# Top_Level.net
KiCad netlist of a schematic drawn in Altium Designer
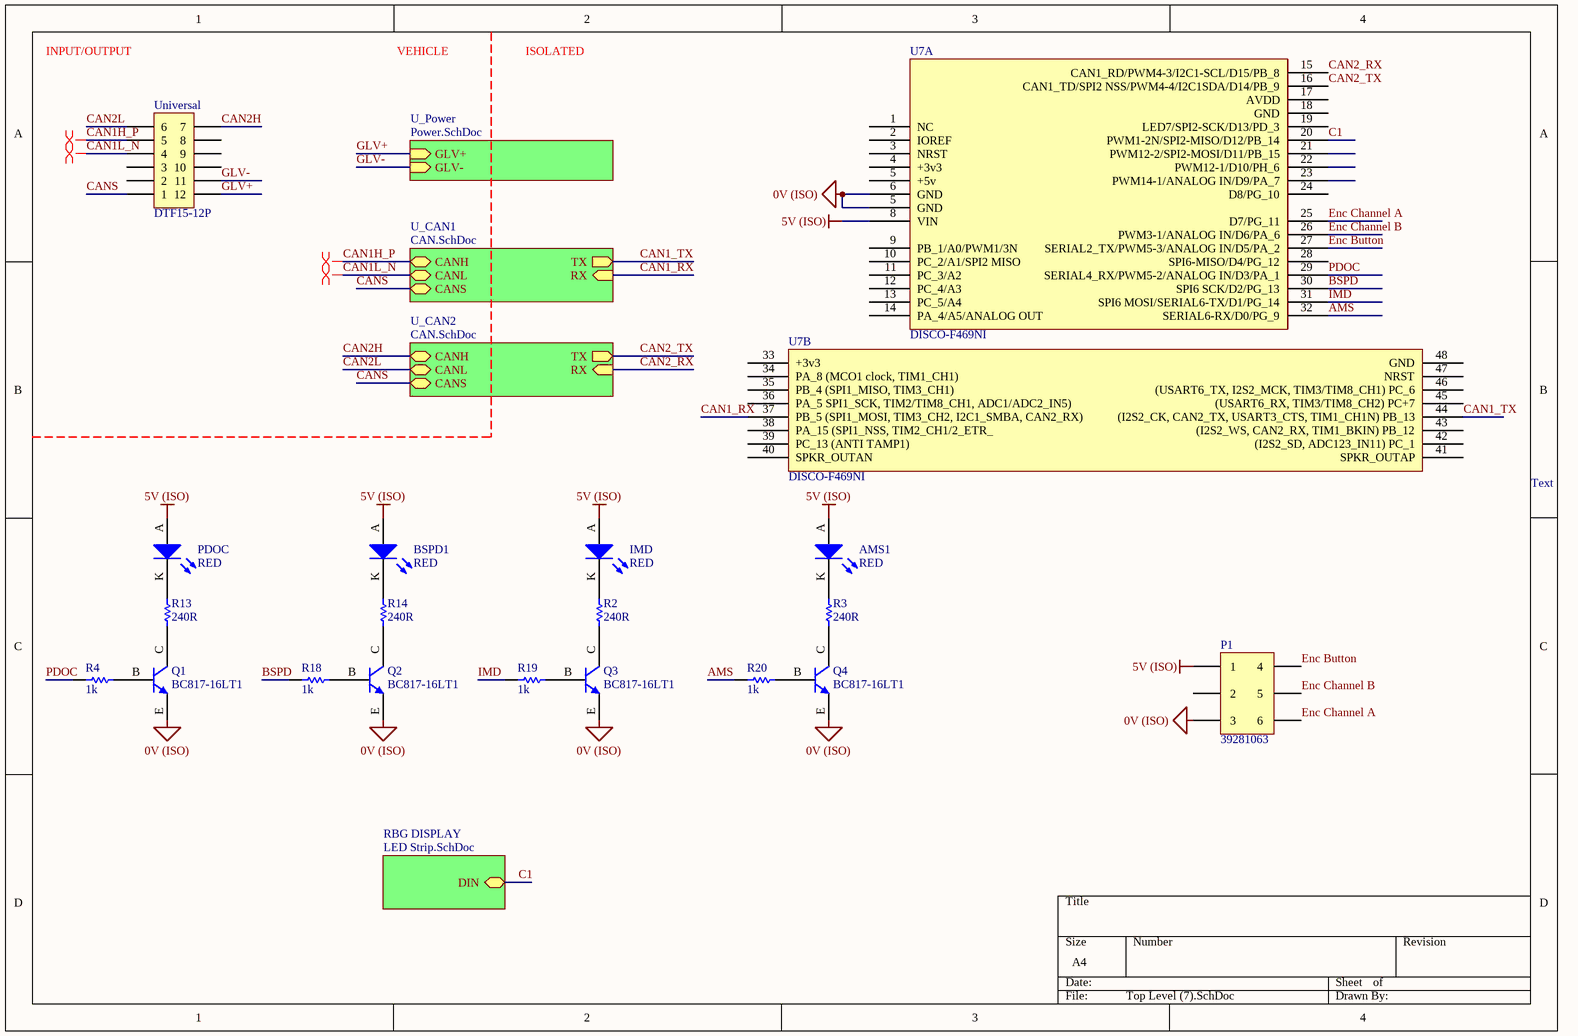
[diagram p0: Top Level (7).SchDoc]

(export (version "E")
  (design (tool "Eeschema 10.0.6"))
  (components
    (comp (ref "AMS1")
      (value "RED")
      (footprint "5MM LED")
      (description "LED RED CLEAR 5MM ROUND T/H")
      (fields (field (name "PART NUMBER") "C503B-GAN-CB0F0791") (field (name "MANUFACTURER") "Cree Inc."))
      (libsource (lib "ts_19-standard-library") (part "LED"))
    )
    (comp (ref "BSPD1")
      (value "RED")
      (footprint "5MM LED")
      (description "LED RED CLEAR 5MM ROUND T/H")
      (fields (field (name "PART NUMBER") "C503B-GAN-CB0F0791") (field (name "MANUFACTURER") "Cree Inc."))
      (libsource (lib "ts_19-standard-library") (part "LED"))
    )
    (comp (ref "IMD")
      (value "RED")
      (footprint "5MM LED")
      (description "LED RED CLEAR 5MM ROUND T/H")
      (fields (field (name "PART NUMBER") "C503B-GAN-CB0F0791") (field (name "MANUFACTURER") "Cree Inc."))
      (libsource (lib "ts_19-standard-library") (part "LED"))
    )
    (comp (ref "P1")
      (value "39281063")
      (footprint "39281063")
      (description "Mini-Fit VERT 3x2")
      (fields (field (name "DIGIKEY PART NUMBER") "WM3802-ND") (field (name "CONTACT") "Gold"))
      (libsource (lib "ts_19-standard-connectors") (part "39281063"))
    )
    (comp (ref "PDOC")
      (value "RED")
      (footprint "5MM LED")
      (description "LED RED CLEAR 5MM ROUND T/H")
      (fields (field (name "PART NUMBER") "C503B-GAN-CB0F0791") (field (name "MANUFACTURER") "Cree Inc."))
      (libsource (lib "ts_19-standard-library") (part "LED"))
    )
    (comp (ref "Q1")
      (value "BC817-16LT1")
      (footprint "ON SOT-23 BJT")
      (description "300mW  BJT NPN Transistor")
      (fields
        (field (name "MANUFACTURER") "ON Semiconductor")
        (field (name "DIGIKEY PART NUMBER") "BC817-16LT1OSTR-ND")
      )
      (libsource (lib "ts_19-standard-library") (part "NPN"))
    )
    (comp (ref "Q2")
      (value "BC817-16LT1")
      (footprint "ON SOT-23 BJT")
      (description "300mW  BJT NPN Transistor")
      (fields
        (field (name "MANUFACTURER") "ON Semiconductor")
        (field (name "DIGIKEY PART NUMBER") "BC817-16LT1OSTR-ND")
      )
      (libsource (lib "ts_19-standard-library") (part "NPN"))
    )
    (comp (ref "Q3")
      (value "BC817-16LT1")
      (footprint "ON SOT-23 BJT")
      (description "300mW  BJT NPN Transistor")
      (fields
        (field (name "MANUFACTURER") "ON Semiconductor")
        (field (name "DIGIKEY PART NUMBER") "BC817-16LT1OSTR-ND")
      )
      (libsource (lib "ts_19-standard-library") (part "NPN"))
    )
    (comp (ref "Q4")
      (value "BC817-16LT1")
      (footprint "ON SOT-23 BJT")
      (description "300mW  BJT NPN Transistor")
      (fields
        (field (name "MANUFACTURER") "ON Semiconductor")
        (field (name "DIGIKEY PART NUMBER") "BC817-16LT1OSTR-ND")
      )
      (libsource (lib "ts_19-standard-library") (part "NPN"))
    )
    (comp (ref "R2")
      (value "240R")
      (footprint "0805")
      (fields
        (field (name "PART NUMBER") "RC0805FR07240RL")
        (field (name "MANUFACTURER") "YAGEO")
        (field (name "TOLERANCE") "0.01")
      )
      (libsource (lib "ts_19-standard-library") (part "Resistor"))
    )
    (comp (ref "R3")
      (value "240R")
      (footprint "0805")
      (fields
        (field (name "PART NUMBER") "RC0805FR07240RL")
        (field (name "MANUFACTURER") "YAGEO")
        (field (name "TOLERANCE") "0.01")
      )
      (libsource (lib "ts_19-standard-library") (part "Resistor"))
    )
    (comp (ref "R4")
      (value "1k")
      (footprint "0805")
      (fields
        (field (name "PART NUMBER") "RC0805FR071KL")
        (field (name "MANUFACTURER") "YAGEO")
        (field (name "TOLERANCE") "0.01")
      )
      (libsource (lib "ts_19-standard-library") (part "Resistor"))
    )
    (comp (ref "R13")
      (value "240R")
      (footprint "0805")
      (fields
        (field (name "PART NUMBER") "RC0805FR07240RL")
        (field (name "MANUFACTURER") "YAGEO")
        (field (name "TOLERANCE") "0.01")
      )
      (libsource (lib "ts_19-standard-library") (part "Resistor"))
    )
    (comp (ref "R14")
      (value "240R")
      (footprint "0805")
      (fields
        (field (name "PART NUMBER") "RC0805FR07240RL")
        (field (name "MANUFACTURER") "YAGEO")
        (field (name "TOLERANCE") "0.01")
      )
      (libsource (lib "ts_19-standard-library") (part "Resistor"))
    )
    (comp (ref "R18")
      (value "1k")
      (footprint "0805")
      (fields
        (field (name "PART NUMBER") "RC0805FR071KL")
        (field (name "MANUFACTURER") "YAGEO")
        (field (name "TOLERANCE") "0.01")
      )
      (libsource (lib "ts_19-standard-library") (part "Resistor"))
    )
    (comp (ref "R19")
      (value "1k")
      (footprint "0805")
      (fields
        (field (name "PART NUMBER") "RC0805FR071KL")
        (field (name "MANUFACTURER") "YAGEO")
        (field (name "TOLERANCE") "0.01")
      )
      (libsource (lib "ts_19-standard-library") (part "Resistor"))
    )
    (comp (ref "R20")
      (value "1k")
      (footprint "0805")
      (fields
        (field (name "PART NUMBER") "RC0805FR071KL")
        (field (name "MANUFACTURER") "YAGEO")
        (field (name "TOLERANCE") "0.01")
      )
      (libsource (lib "ts_19-standard-library") (part "Resistor"))
    )
    (comp (ref "U7")
      (value "DISCO-F469NI")
      (footprint "DISCO-F469NI")
      (fields
        (field (name "MANUFACTURER") "STMicroelectronics")
        (field (name "DIGIKEY PART NUMBER") "497-15990-ND")
      )
      (libsource (lib "ts_19-standard-library") (part "DISCO-F469NI"))
    )
    (comp (ref "Universal")
      (value "DTF15-12P")
      (footprint "DTF15-12P")
      (fields (field (name "DIGIKEY PART NUMBER") "1734-1647-ND") (field (name "CONTACT") "Copper Alloy"))
      (libsource (lib "ts_20-standard-connectors") (part "DT15-12P"))
    )
  )
  (nets
    (net (code "1") (name "/AMS") (class "Default")
      (node (ref "R20") (pin "1") (pinfunction "1_1") (pintype "passive"))
      (node (ref "U7") (pin "32") (pinfunction "SERIAL6-RX/D0/PG_9_32") (pintype "passive"))
    )
    (net (code "2") (name "/BSPD") (class "Default")
      (node (ref "R18") (pin "1") (pinfunction "1_1") (pintype "passive"))
      (node (ref "U7") (pin "30") (pinfunction "SPI6_SCK/D2/PG_13_30") (pintype "passive"))
    )
    (net (code "3") (name "/C1") (class "Default")
      (node (ref "U7") (pin "20") (pinfunction "PWM1-2N/SPI2-MISO/D12/PB_14_20") (pintype "passive"))
    )
    (net (code "4") (name "/CAN1H_P") (class "Default")
      (node (ref "Universal") (pin "5") (pinfunction "5_5") (pintype "power_in"))
    )
    (net (code "5") (name "/CAN1L_N") (class "Default")
      (node (ref "Universal") (pin "4") (pinfunction "4_4") (pintype "power_in"))
    )
    (net (code "6") (name "/CAN1_RX") (class "Default")
      (node (ref "U7") (pin "37") (pinfunction "PB_5_(SPI1_MOSI,_TIM3_CH2,_I2C1_SMBA,_CAN2_RX)_37") (pintype "passive"))
    )
    (net (code "7") (name "/CAN1_TX") (class "Default")
      (node (ref "U7") (pin "44") (pinfunction "(I2S2_CK,_CAN2_TX,_USART3_CTS,_TIM1_CH1N)_PB_13_44") (pintype "passive"))
    )
    (net (code "8") (name "/CAN2H") (class "Default")
      (node (ref "Universal") (pin "7") (pinfunction "7_7") (pintype "passive"))
    )
    (net (code "9") (name "/CAN2L") (class "Default")
      (node (ref "Universal") (pin "6") (pinfunction "6_6") (pintype "power_in"))
    )
    (net (code "10") (name "/CAN2_RX") (class "Default")
      (node (ref "U7") (pin "15") (pinfunction "CAN1_RD/PWM4-3/I2C1-SCL/D15/PB_8_15") (pintype "passive"))
    )
    (net (code "11") (name "/CAN2_TX") (class "Default")
      (node (ref "U7") (pin "16") (pinfunction "CAN1_TD/SPI2_NSS/PWM4-4/I2C1SDA/D14/PB_9_16") (pintype "passive"))
    )
    (net (code "12") (name "/CANS") (class "Default")
      (node (ref "Universal") (pin "1") (pinfunction "1_1") (pintype "power_in"))
    )
    (net (code "13") (name "/Enc Button") (class "Default")
      (node (ref "P1") (pin "4") (pinfunction "4_4") (pintype "passive"))
      (node (ref "U7") (pin "27") (pinfunction "SERIAL2_TX/PWM5-3/ANALOG_IN/D5/PA_2_27") (pintype "passive"))
    )
    (net (code "14") (name "/Enc Channel A") (class "Default")
      (node (ref "P1") (pin "6") (pinfunction "6_6") (pintype "passive"))
      (node (ref "U7") (pin "25") (pinfunction "D7/PG_11_25") (pintype "passive"))
    )
    (net (code "15") (name "/Enc Channel B") (class "Default")
      (node (ref "P1") (pin "5") (pinfunction "5_5") (pintype "passive"))
      (node (ref "U7") (pin "26") (pinfunction "PWM3-1/ANALOG_IN/D6/PA_6_26") (pintype "passive"))
    )
    (net (code "16") (name "/GLV+") (class "Default")
      (node (ref "Universal") (pin "12") (pinfunction "12_12") (pintype "passive"))
    )
    (net (code "17") (name "/GLV-") (class "Default")
      (node (ref "Universal") (pin "11") (pinfunction "11_11") (pintype "passive"))
    )
    (net (code "18") (name "/IMD") (class "Default")
      (node (ref "R19") (pin "1") (pinfunction "1_1") (pintype "passive"))
      (node (ref "U7") (pin "31") (pinfunction "SPI6_MOSI/SERIAL6-TX/D1/PG_14_31") (pintype "passive"))
    )
    (net (code "19") (name "/PDOC") (class "Default")
      (node (ref "R4") (pin "1") (pinfunction "1_1") (pintype "passive"))
      (node (ref "U7") (pin "29") (pinfunction "SERIAL4_RX/PWM5-2/ANALOG_IN/D3/PA_1_29") (pintype "passive"))
    )
    (net (code "20") (name "0V (ISO)") (class "Default")
      (node (ref "P1") (pin "3") (pinfunction "3_3") (pintype "passive"))
      (node (ref "Q1") (pin "E") (pinfunction "E_E") (pintype "passive"))
      (node (ref "Q2") (pin "E") (pinfunction "E_E") (pintype "passive"))
      (node (ref "Q3") (pin "E") (pinfunction "E_E") (pintype "passive"))
      (node (ref "Q4") (pin "E") (pinfunction "E_E") (pintype "passive"))
      (node (ref "U7") (pin "5") (pinfunction "GND_5") (pintype "passive"))
      (node (ref "U7") (pin "6") (pinfunction "GND_6") (pintype "passive"))
    )
    (net (code "21") (name "5V (ISO)") (class "Default")
      (node (ref "AMS1") (pin "A") (pinfunction "A_A") (pintype "passive"))
      (node (ref "BSPD1") (pin "A") (pinfunction "A_A") (pintype "passive"))
      (node (ref "IMD") (pin "A") (pinfunction "A_A") (pintype "passive"))
      (node (ref "P1") (pin "1") (pinfunction "1_1") (pintype "passive"))
      (node (ref "PDOC") (pin "A") (pinfunction "A_A") (pintype "passive"))
      (node (ref "U7") (pin "8") (pinfunction "VIN_8") (pintype "passive"))
    )
    (net (code "22") (name "Net-(AMS1-PadK)") (class "Default")
      (node (ref "AMS1") (pin "K") (pinfunction "K_K") (pintype "passive"))
      (node (ref "R3") (pin "2") (pinfunction "2_2") (pintype "passive"))
    )
    (net (code "23") (name "Net-(BSPD1-PadK)") (class "Default")
      (node (ref "BSPD1") (pin "K") (pinfunction "K_K") (pintype "passive"))
      (node (ref "R14") (pin "2") (pinfunction "2_2") (pintype "passive"))
    )
    (net (code "24") (name "Net-(IMD-PadK)") (class "Default")
      (node (ref "IMD") (pin "K") (pinfunction "K_K") (pintype "passive"))
      (node (ref "R2") (pin "2") (pinfunction "2_2") (pintype "passive"))
    )
    (net (code "25") (name "Net-(PDOC-PadK)") (class "Default")
      (node (ref "PDOC") (pin "K") (pinfunction "K_K") (pintype "passive"))
      (node (ref "R13") (pin "2") (pinfunction "2_2") (pintype "passive"))
    )
    (net (code "26") (name "Net-(Q1-PadB)") (class "Default")
      (node (ref "Q1") (pin "B") (pinfunction "B_B") (pintype "passive"))
      (node (ref "R4") (pin "2") (pinfunction "2_2") (pintype "passive"))
    )
    (net (code "27") (name "Net-(Q1-PadC)") (class "Default")
      (node (ref "Q1") (pin "C") (pinfunction "C_C") (pintype "passive"))
      (node (ref "R13") (pin "1") (pinfunction "1_1") (pintype "passive"))
    )
    (net (code "28") (name "Net-(Q2-PadB)") (class "Default")
      (node (ref "Q2") (pin "B") (pinfunction "B_B") (pintype "passive"))
      (node (ref "R18") (pin "2") (pinfunction "2_2") (pintype "passive"))
    )
    (net (code "29") (name "Net-(Q2-PadC)") (class "Default")
      (node (ref "Q2") (pin "C") (pinfunction "C_C") (pintype "passive"))
      (node (ref "R14") (pin "1") (pinfunction "1_1") (pintype "passive"))
    )
    (net (code "30") (name "Net-(Q3-PadB)") (class "Default")
      (node (ref "Q3") (pin "B") (pinfunction "B_B") (pintype "passive"))
      (node (ref "R19") (pin "2") (pinfunction "2_2") (pintype "passive"))
    )
    (net (code "31") (name "Net-(Q3-PadC)") (class "Default")
      (node (ref "Q3") (pin "C") (pinfunction "C_C") (pintype "passive"))
      (node (ref "R2") (pin "1") (pinfunction "1_1") (pintype "passive"))
    )
    (net (code "32") (name "Net-(Q4-PadB)") (class "Default")
      (node (ref "Q4") (pin "B") (pinfunction "B_B") (pintype "passive"))
      (node (ref "R20") (pin "2") (pinfunction "2_2") (pintype "passive"))
    )
    (net (code "33") (name "Net-(Q4-PadC)") (class "Default")
      (node (ref "Q4") (pin "C") (pinfunction "C_C") (pintype "passive"))
      (node (ref "R3") (pin "1") (pinfunction "1_1") (pintype "passive"))
    )
    (net (code "34") (name "unconnected-(P1-Pad2)") (class "Default")
      (node (ref "P1") (pin "2") (pinfunction "2_2") (pintype "passive"))
    )
    (net (code "35") (name "unconnected-(U7A-+3v3-Pad4)") (class "Default")
      (node (ref "U7") (pin "4") (pinfunction "+3v3_4") (pintype "passive"))
    )
    (net (code "36") (name "unconnected-(U7A-+5v-Pad5)") (class "Default")
      (node (ref "U7") (pin "5") (pinfunction "+5v_5") (pintype "passive"))
    )
    (net (code "37") (name "unconnected-(U7A-AVDD-Pad17)") (class "Default")
      (node (ref "U7") (pin "17") (pinfunction "AVDD_17") (pintype "passive"))
    )
    (net (code "38") (name "unconnected-(U7A-D8{slash}PG_10-Pad24)") (class "Default")
      (node (ref "U7") (pin "24") (pinfunction "D8/PG_10_24") (pintype "passive"))
    )
    (net (code "39") (name "unconnected-(U7A-GND-Pad18)") (class "Default")
      (node (ref "U7") (pin "18") (pinfunction "GND_18") (pintype "passive"))
    )
    (net (code "40") (name "unconnected-(U7A-IOREF-Pad2)") (class "Default")
      (node (ref "U7") (pin "2") (pinfunction "IOREF_2") (pintype "passive"))
    )
    (net (code "41") (name "unconnected-(U7A-LED7{slash}SPI2-SCK{slash}D13{slash}PD_3-Pad19)") (class "Default")
      (node (ref "U7") (pin "19") (pinfunction "LED7/SPI2-SCK/D13/PD_3_19") (pintype "passive"))
    )
    (net (code "42") (name "unconnected-(U7A-NC-Pad1)") (class "Default")
      (node (ref "U7") (pin "1") (pinfunction "NC_1") (pintype "passive"))
    )
    (net (code "43") (name "unconnected-(U7A-NRST-Pad3)") (class "Default")
      (node (ref "U7") (pin "3") (pinfunction "NRST_3") (pintype "passive"))
    )
    (net (code "44") (name "unconnected-(U7A-PA_4{slash}A5{slash}ANALOG_OUT-Pad14)") (class "Default")
      (node (ref "U7") (pin "14") (pinfunction "PA_4/A5/ANALOG_OUT_14") (pintype "passive"))
    )
    (net (code "45") (name "unconnected-(U7A-PB_1{slash}A0{slash}PWM1{slash}3N-Pad9)") (class "Default")
      (node (ref "U7") (pin "9") (pinfunction "PB_1/A0/PWM1/3N_9") (pintype "passive"))
    )
    (net (code "46") (name "unconnected-(U7A-PC_2{slash}A1{slash}SPI2_MISO-Pad10)") (class "Default")
      (node (ref "U7") (pin "10") (pinfunction "PC_2/A1/SPI2_MISO_10") (pintype "passive"))
    )
    (net (code "47") (name "unconnected-(U7A-PC_3{slash}A2-Pad11)") (class "Default")
      (node (ref "U7") (pin "11") (pinfunction "PC_3/A2_11") (pintype "passive"))
    )
    (net (code "48") (name "unconnected-(U7A-PC_4{slash}A3-Pad12)") (class "Default")
      (node (ref "U7") (pin "12") (pinfunction "PC_4/A3_12") (pintype "passive"))
    )
    (net (code "49") (name "unconnected-(U7A-PC_5{slash}A4-Pad13)") (class "Default")
      (node (ref "U7") (pin "13") (pinfunction "PC_5/A4_13") (pintype "passive"))
    )
    (net (code "50") (name "unconnected-(U7A-PWM12-1{slash}D10{slash}PH_6-Pad22)") (class "Default")
      (node (ref "U7") (pin "22") (pinfunction "PWM12-1/D10/PH_6_22") (pintype "passive"))
    )
    (net (code "51") (name "unconnected-(U7A-PWM12-2{slash}SPI2-MOSI{slash}D11{slash}PB_15-Pad21)") (class "Default")
      (node (ref "U7") (pin "21") (pinfunction "PWM12-2/SPI2-MOSI/D11/PB_15_21") (pintype "passive"))
    )
    (net (code "52") (name "unconnected-(U7A-PWM14-1{slash}ANALOG_IN{slash}D9{slash}PA_7-Pad23)") (class "Default")
      (node (ref "U7") (pin "23") (pinfunction "PWM14-1/ANALOG_IN/D9/PA_7_23") (pintype "passive"))
    )
    (net (code "53") (name "unconnected-(U7A-SPI6-MISO{slash}D4{slash}PG_12-Pad28)") (class "Default")
      (node (ref "U7") (pin "28") (pinfunction "SPI6-MISO/D4/PG_12_28") (pintype "passive"))
    )
    (net (code "54") (name "unconnected-(U7B-(I2S2_SD,_ADC123_IN11)_PC_1-Pad42)") (class "Default")
      (node (ref "U7") (pin "42") (pinfunction "(I2S2_SD,_ADC123_IN11)_PC_1_42") (pintype "passive"))
    )
    (net (code "55") (name "unconnected-(U7B-(I2S2_WS,_CAN2_RX,_TIM1_BKIN)_PB_12-Pad43)") (class "Default")
      (node (ref "U7") (pin "43") (pinfunction "(I2S2_WS,_CAN2_RX,_TIM1_BKIN)_PB_12_43") (pintype "passive"))
    )
    (net (code "56") (name "unconnected-(U7B-(USART6_RX,_TIM3{slash}TIM8_CH2)_PC+7-Pad45)") (class "Default")
      (node (ref "U7") (pin "45") (pinfunction "(USART6_RX,_TIM3/TIM8_CH2)_PC+7_45") (pintype "passive"))
    )
    (net (code "57") (name "unconnected-(U7B-(USART6_TX,_I2S2_MCK,_TIM3{slash}TIM8_CH1)_PC_6-Pad46)") (class "Default")
      (node (ref "U7") (pin "46") (pinfunction "(USART6_TX,_I2S2_MCK,_TIM3/TIM8_CH1)_PC_6_46") (pintype "passive"))
    )
    (net (code "58") (name "unconnected-(U7B-+3v3-Pad33)") (class "Default")
      (node (ref "U7") (pin "33") (pinfunction "+3v3_33") (pintype "passive"))
    )
    (net (code "59") (name "unconnected-(U7B-GND-Pad48)") (class "Default")
      (node (ref "U7") (pin "48") (pinfunction "GND_48") (pintype "passive"))
    )
    (net (code "60") (name "unconnected-(U7B-NRST-Pad47)") (class "Default")
      (node (ref "U7") (pin "47") (pinfunction "NRST_47") (pintype "passive"))
    )
    (net (code "61") (name "unconnected-(U7B-PA_5_SPI1_SCK,_TIM2{slash}TIM8_CH1,_ADC1{slash}ADC2_IN5)-Pad36)") (class "Default")
      (node (ref "U7") (pin "36") (pinfunction "PA_5_SPI1_SCK,_TIM2/TIM8_CH1,_ADC1/ADC2_IN5)_36") (pintype "passive"))
    )
    (net (code "62") (name "unconnected-(U7B-PA_8_(MCO1_clock,_TIM1_CH1)-Pad34)") (class "Default")
      (node (ref "U7") (pin "34") (pinfunction "PA_8_(MCO1_clock,_TIM1_CH1)_34") (pintype "passive"))
    )
    (net (code "63") (name "unconnected-(U7B-PA_15_(SPI1_NSS,_TIM2_CH1{slash}2_ETR_-Pad38)") (class "Default")
      (node (ref "U7") (pin "38") (pinfunction "PA_15_(SPI1_NSS,_TIM2_CH1/2_ETR__38") (pintype "passive"))
    )
    (net (code "64") (name "unconnected-(U7B-PB_4_(SPI1_MISO,_TIM3_CH1)-Pad35)") (class "Default")
      (node (ref "U7") (pin "35") (pinfunction "PB_4_(SPI1_MISO,_TIM3_CH1)_35") (pintype "passive"))
    )
    (net (code "65") (name "unconnected-(U7B-PC_13_(ANTI_TAMP1)-Pad39)") (class "Default")
      (node (ref "U7") (pin "39") (pinfunction "PC_13_(ANTI_TAMP1)_39") (pintype "passive"))
    )
    (net (code "66") (name "unconnected-(U7B-SPKR_OUTAN-Pad40)") (class "Default")
      (node (ref "U7") (pin "40") (pinfunction "SPKR_OUTAN_40") (pintype "passive"))
    )
    (net (code "67") (name "unconnected-(U7B-SPKR_OUTAP-Pad41)") (class "Default")
      (node (ref "U7") (pin "41") (pinfunction "SPKR_OUTAP_41") (pintype "passive"))
    )
    (net (code "68") (name "unconnected-(Universal-Pad2)") (class "Default")
      (node (ref "Universal") (pin "2") (pinfunction "2_2") (pintype "power_in"))
    )
    (net (code "69") (name "unconnected-(Universal-Pad3)") (class "Default")
      (node (ref "Universal") (pin "3") (pinfunction "3_3") (pintype "power_in"))
    )
    (net (code "70") (name "unconnected-(Universal-Pad8)") (class "Default")
      (node (ref "Universal") (pin "8") (pinfunction "8_8") (pintype "passive"))
    )
    (net (code "71") (name "unconnected-(Universal-Pad9)") (class "Default")
      (node (ref "Universal") (pin "9") (pinfunction "9_9") (pintype "passive"))
    )
    (net (code "72") (name "unconnected-(Universal-Pad10)") (class "Default")
      (node (ref "Universal") (pin "10") (pinfunction "10_10") (pintype "passive"))
    )
  )
)
